# smartmeter.net
KiCad netlist of a schematic drawn in EAGLE
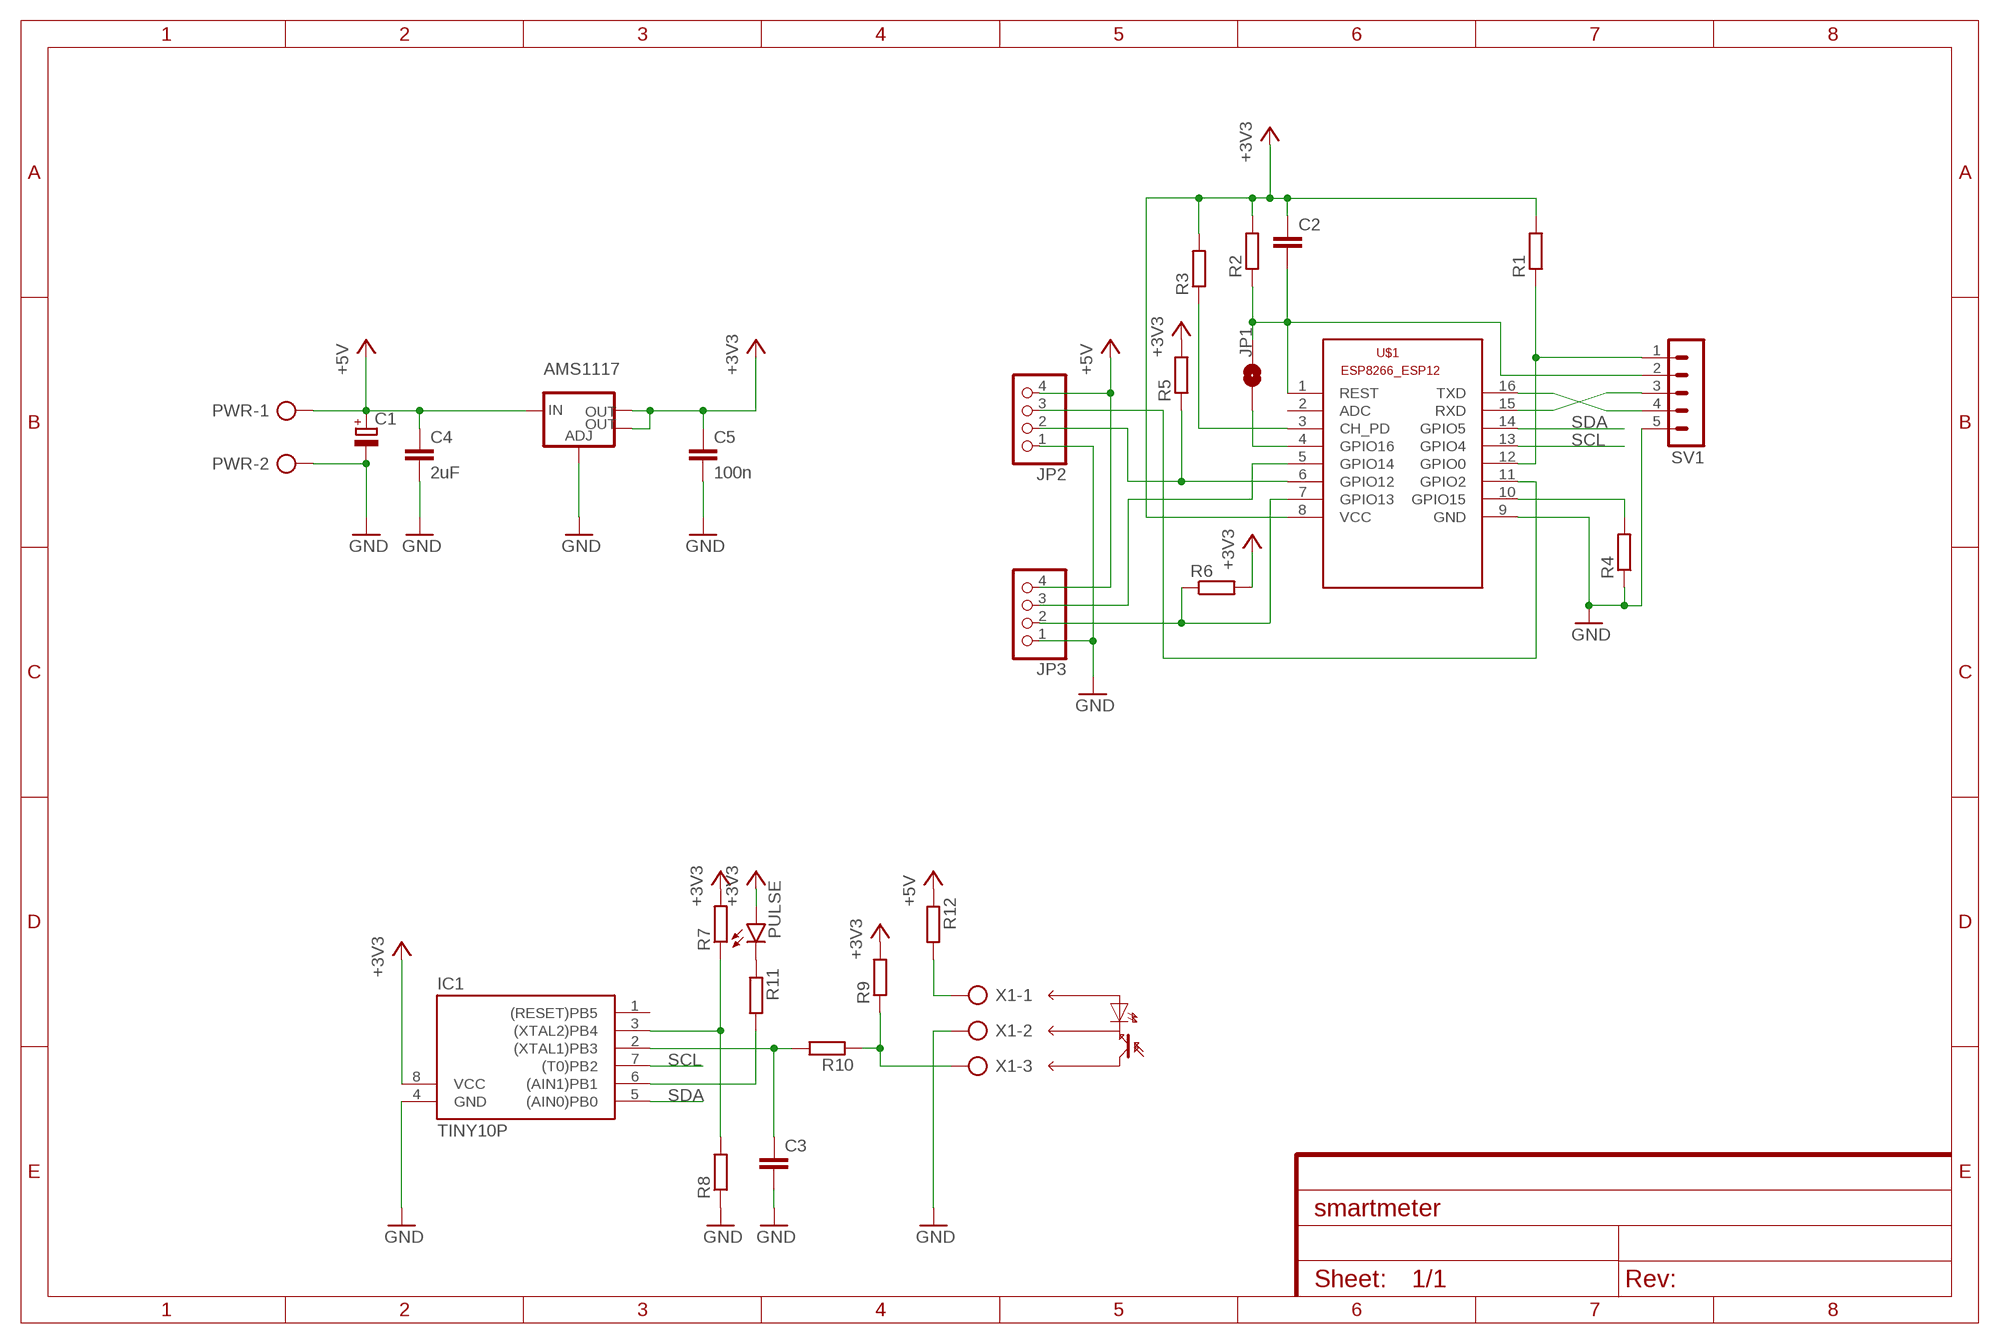
[diagram p0: schematic, sheet 1]

(export (version "E")
  (design (tool "Eeschema 10.0.6"))
  (components
    (comp (ref "AMS1117")
      (value "V_REG_LM1117SOT223")
      (footprint "eagle-import:SOT223")
      (libsource (lib "eagle-import") (part "V_REG_LM1117SOT223"))
    )
    (comp (ref "C1")
      (value "CPOL-EUE3.5-10")
      (footprint "eagle-import:E3,5-10")
      (libsource (lib "eagle-import") (part "CPOL-EUE3.5-10"))
    )
    (comp (ref "C2")
      (value "C-EU050-025X075")
      (footprint "eagle-import:C050-025X075")
      (libsource (lib "eagle-import") (part "C-EU050-025X075"))
    )
    (comp (ref "C3")
      (value "C-EU050-025X075")
      (footprint "eagle-import:C050-025X075")
      (libsource (lib "eagle-import") (part "C-EU050-025X075"))
    )
    (comp (ref "C4")
      (value "2uF")
      (footprint "eagle-import:C025-025X050")
      (libsource (lib "eagle-import") (part "C-EU025-025X050"))
    )
    (comp (ref "C5")
      (value "100n")
      (footprint "eagle-import:C025-025X050")
      (libsource (lib "eagle-import") (part "C-EU025-025X050"))
    )
    (comp (ref "IC1")
      (value "TINY10P")
      (footprint "eagle-import:DIL08")
      (libsource (lib "eagle-import") (part "TINY10P"))
    )
    (comp (ref "JP1")
      (value "JUMPER-SMT_2_NO_SILK")
      (footprint "eagle-import:SMT-JUMPER_2_NO_SILK")
      (libsource (lib "eagle-import") (part "JUMPER-SMT_2_NO_SILK"))
    )
    (comp (ref "JP2")
      (value "PINHD-1X4/90")
      (footprint "eagle-import:1X04_90")
      (libsource (lib "eagle-import") (part "PINHD-1X4/90"))
    )
    (comp (ref "JP3")
      (value "PINHD-1X4/90")
      (footprint "eagle-import:1X04_90")
      (libsource (lib "eagle-import") (part "PINHD-1X4/90"))
    )
    (comp (ref "PULSE")
      (value "LED5MM")
      (footprint "eagle-import:LED5MM")
      (libsource (lib "eagle-import") (part "LED5MM"))
    )
    (comp (ref "PWR")
      (value "AK500/2")
      (footprint "eagle-import:AK500_2")
      (libsource (lib "eagle-import") (part "AK500/2"))
    )
    (comp (ref "R1")
      (value "R-EU_0207/10")
      (footprint "eagle-import:0207_10")
      (libsource (lib "eagle-import") (part "R-EU_0207/10"))
    )
    (comp (ref "R2")
      (value "R-EU_0207/10")
      (footprint "eagle-import:0207_10")
      (libsource (lib "eagle-import") (part "R-EU_0207/10"))
    )
    (comp (ref "R3")
      (value "R-EU_0207/10")
      (footprint "eagle-import:0207_10")
      (libsource (lib "eagle-import") (part "R-EU_0207/10"))
    )
    (comp (ref "R4")
      (value "R-EU_0207/10")
      (footprint "eagle-import:0207_10")
      (libsource (lib "eagle-import") (part "R-EU_0207/10"))
    )
    (comp (ref "R5")
      (value "R-EU_0207/10")
      (footprint "eagle-import:0207_10")
      (libsource (lib "eagle-import") (part "R-EU_0207/10"))
    )
    (comp (ref "R6")
      (value "R-EU_0207/10")
      (footprint "eagle-import:0207_10")
      (libsource (lib "eagle-import") (part "R-EU_0207/10"))
    )
    (comp (ref "R7")
      (value "R-EU_0207/10")
      (footprint "eagle-import:0207_10")
      (libsource (lib "eagle-import") (part "R-EU_0207/10"))
    )
    (comp (ref "R8")
      (value "R-EU_0207/10")
      (footprint "eagle-import:0207_10")
      (libsource (lib "eagle-import") (part "R-EU_0207/10"))
    )
    (comp (ref "R9")
      (value "R-EU_0207/10")
      (footprint "eagle-import:0207_10")
      (libsource (lib "eagle-import") (part "R-EU_0207/10"))
    )
    (comp (ref "R10")
      (value "R-EU_0207/10")
      (footprint "eagle-import:0207_10")
      (libsource (lib "eagle-import") (part "R-EU_0207/10"))
    )
    (comp (ref "R11")
      (value "R-EU_0207/10")
      (footprint "eagle-import:0207_10")
      (libsource (lib "eagle-import") (part "R-EU_0207/10"))
    )
    (comp (ref "R12")
      (value "R-EU_0207/10")
      (footprint "eagle-import:0207_10")
      (libsource (lib "eagle-import") (part "R-EU_0207/10"))
    )
    (comp (ref "SV1")
      (value "MA05-1")
      (footprint "eagle-import:MA05-1")
      (libsource (lib "eagle-import") (part "MA05-1"))
    )
    (comp (ref "U$1")
      (value "ESP8266-12")
      (footprint "eagle-import:ESP8266-ESP12")
      (libsource (lib "eagle-import") (part "ESP8266-12"))
    )
    (comp (ref "X1")
      (value "AK500/3")
      (footprint "eagle-import:AK500_3")
      (libsource (lib "eagle-import") (part "AK500/3"))
    )
  )
  (nets
    (net (code "1") (name "+3V3") (class "Default")
      (node (ref "AMS1117") (pin "2") (pinfunction "OUT_2") (pintype "output"))
      (node (ref "AMS1117") (pin "4") (pinfunction "OUT_4") (pintype "output"))
      (node (ref "C2") (pin "1") (pinfunction "1_1") (pintype "passive"))
      (node (ref "C5") (pin "1") (pinfunction "1_1") (pintype "passive"))
      (node (ref "IC1") (pin "8") (pinfunction "VCC_8") (pintype "power_in"))
      (node (ref "PULSE") (pin "A") (pinfunction "A_A") (pintype "passive"))
      (node (ref "R1") (pin "2") (pinfunction "2_2") (pintype "passive"))
      (node (ref "R2") (pin "2") (pinfunction "2_2") (pintype "passive"))
      (node (ref "R3") (pin "2") (pinfunction "2_2") (pintype "passive"))
      (node (ref "R5") (pin "2") (pinfunction "2_2") (pintype "passive"))
      (node (ref "R6") (pin "2") (pinfunction "2_2") (pintype "passive"))
      (node (ref "R7") (pin "2") (pinfunction "2_2") (pintype "passive"))
      (node (ref "R9") (pin "2") (pinfunction "2_2") (pintype "passive"))
      (node (ref "U$1") (pin "8") (pinfunction "VCC_8") (pintype "bidirectional"))
    )
    (net (code "2") (name "+5V") (class "Default")
      (node (ref "AMS1117") (pin "3") (pinfunction "IN_3") (pintype "input"))
      (node (ref "C1") (pin "+") (pinfunction "+_+") (pintype "passive"))
      (node (ref "C4") (pin "1") (pinfunction "1_1") (pintype "passive"))
      (node (ref "JP2") (pin "4") (pinfunction "4_4") (pintype "passive"))
      (node (ref "JP3") (pin "4") (pinfunction "4_4") (pintype "passive"))
      (node (ref "PWR") (pin "1") (pinfunction "KL_1") (pintype "passive"))
      (node (ref "R12") (pin "1") (pinfunction "1_1") (pintype "passive"))
    )
    (net (code "3") (name "/SCL") (class "Default")
      (node (ref "IC1") (pin "7") (pinfunction "(T0)PB2_7") (pintype "bidirectional"))
      (node (ref "U$1") (pin "13") (pinfunction "GPIO4_13") (pintype "bidirectional"))
    )
    (net (code "4") (name "/SDA") (class "Default")
      (node (ref "IC1") (pin "5") (pinfunction "(AIN0)PB0_5") (pintype "bidirectional"))
      (node (ref "U$1") (pin "14") (pinfunction "GPIO5_14") (pintype "bidirectional"))
    )
    (net (code "5") (name "GND") (class "Default")
      (node (ref "AMS1117") (pin "1") (pinfunction "ADJ_1") (pintype "input"))
      (node (ref "C1") (pin "-") (pinfunction "-_-") (pintype "passive"))
      (node (ref "C3") (pin "2") (pinfunction "2_2") (pintype "passive"))
      (node (ref "C4") (pin "2") (pinfunction "2_2") (pintype "passive"))
      (node (ref "C5") (pin "2") (pinfunction "2_2") (pintype "passive"))
      (node (ref "IC1") (pin "4") (pinfunction "GND_4") (pintype "power_in"))
      (node (ref "JP2") (pin "1") (pinfunction "1_1") (pintype "passive"))
      (node (ref "JP3") (pin "1") (pinfunction "1_1") (pintype "passive"))
      (node (ref "PWR") (pin "2") (pinfunction "KL_2") (pintype "passive"))
      (node (ref "R4") (pin "1") (pinfunction "1_1") (pintype "passive"))
      (node (ref "R8") (pin "1") (pinfunction "1_1") (pintype "passive"))
      (node (ref "SV1") (pin "5") (pinfunction "5_5") (pintype "passive"))
      (node (ref "U$1") (pin "9") (pinfunction "GND_9") (pintype "bidirectional"))
      (node (ref "X1") (pin "2") (pinfunction "KL_2") (pintype "passive"))
    )
    (net (code "6") (name "Net-(IC1-(AIN1)PB1)") (class "Default")
      (node (ref "IC1") (pin "6") (pinfunction "(AIN1)PB1_6") (pintype "bidirectional"))
      (node (ref "R11") (pin "2") (pinfunction "2_2") (pintype "passive"))
    )
    (net (code "7") (name "Net-(IC1-(XTAL1)PB3)") (class "Default")
      (node (ref "C3") (pin "1") (pinfunction "1_1") (pintype "passive"))
      (node (ref "IC1") (pin "2") (pinfunction "(XTAL1)PB3_2") (pintype "bidirectional"))
      (node (ref "R10") (pin "2") (pinfunction "2_2") (pintype "passive"))
    )
    (net (code "8") (name "Net-(IC1-(XTAL2)PB4)") (class "Default")
      (node (ref "IC1") (pin "3") (pinfunction "(XTAL2)PB4_3") (pintype "bidirectional"))
      (node (ref "R7") (pin "1") (pinfunction "1_1") (pintype "passive"))
      (node (ref "R8") (pin "2") (pinfunction "2_2") (pintype "passive"))
    )
    (net (code "9") (name "Net-(PULSE-C)") (class "Default")
      (node (ref "PULSE") (pin "K") (pinfunction "C_K") (pintype "passive"))
      (node (ref "R11") (pin "1") (pinfunction "1_1") (pintype "passive"))
    )
    (net (code "10") (name "Net-(U$1-CH_PD)") (class "Default")
      (node (ref "R3") (pin "1") (pinfunction "1_1") (pintype "passive"))
      (node (ref "U$1") (pin "3") (pinfunction "CH_PD_3") (pintype "bidirectional"))
    )
    (net (code "11") (name "Net-(U$1-GPIO0)") (class "Default")
      (node (ref "R1") (pin "1") (pinfunction "1_1") (pintype "passive"))
      (node (ref "SV1") (pin "1") (pinfunction "1_1") (pintype "passive"))
      (node (ref "U$1") (pin "12") (pinfunction "GPIO0_12") (pintype "bidirectional"))
    )
    (net (code "12") (name "Net-(U$1-GPIO2)") (class "Default")
      (node (ref "JP2") (pin "3") (pinfunction "3_3") (pintype "passive"))
      (node (ref "U$1") (pin "11") (pinfunction "GPIO2_11") (pintype "bidirectional"))
    )
    (net (code "13") (name "Net-(U$1-GPIO12)") (class "Default")
      (node (ref "JP2") (pin "2") (pinfunction "2_2") (pintype "passive"))
      (node (ref "R5") (pin "1") (pinfunction "1_1") (pintype "passive"))
      (node (ref "U$1") (pin "6") (pinfunction "GPIO12_6") (pintype "bidirectional"))
    )
    (net (code "14") (name "Net-(U$1-GPIO13)") (class "Default")
      (node (ref "JP3") (pin "2") (pinfunction "2_2") (pintype "passive"))
      (node (ref "R6") (pin "1") (pinfunction "1_1") (pintype "passive"))
      (node (ref "U$1") (pin "7") (pinfunction "GPIO13_7") (pintype "bidirectional"))
    )
    (net (code "15") (name "Net-(U$1-GPIO14)") (class "Default")
      (node (ref "JP3") (pin "3") (pinfunction "3_3") (pintype "passive"))
      (node (ref "U$1") (pin "5") (pinfunction "GPIO14_5") (pintype "bidirectional"))
    )
    (net (code "16") (name "Net-(U$1-GPIO15)") (class "Default")
      (node (ref "R4") (pin "2") (pinfunction "2_2") (pintype "passive"))
      (node (ref "U$1") (pin "10") (pinfunction "GPIO15_10") (pintype "bidirectional"))
    )
    (net (code "17") (name "Net-(U$1-GPIO16)") (class "Default")
      (node (ref "JP1") (pin "1") (pinfunction "1_1") (pintype "passive"))
      (node (ref "U$1") (pin "4") (pinfunction "GPIO16_4") (pintype "bidirectional"))
    )
    (net (code "18") (name "Net-(U$1-REST)") (class "Default")
      (node (ref "C2") (pin "2") (pinfunction "2_2") (pintype "passive"))
      (node (ref "JP1") (pin "2") (pinfunction "2_2") (pintype "passive"))
      (node (ref "R2") (pin "1") (pinfunction "1_1") (pintype "passive"))
      (node (ref "SV1") (pin "2") (pinfunction "2_2") (pintype "passive"))
      (node (ref "U$1") (pin "1") (pinfunction "REST_1") (pintype "bidirectional"))
    )
    (net (code "19") (name "Net-(U$1-RXD)") (class "Default")
      (node (ref "SV1") (pin "3") (pinfunction "3_3") (pintype "passive"))
      (node (ref "U$1") (pin "15") (pinfunction "RXD_15") (pintype "bidirectional"))
    )
    (net (code "20") (name "Net-(U$1-TXD)") (class "Default")
      (node (ref "SV1") (pin "4") (pinfunction "4_4") (pintype "passive"))
      (node (ref "U$1") (pin "16") (pinfunction "TXD_16") (pintype "bidirectional"))
    )
    (net (code "21") (name "Net-(X1A-KL)") (class "Default")
      (node (ref "R12") (pin "2") (pinfunction "2_2") (pintype "passive"))
      (node (ref "X1") (pin "1") (pinfunction "KL_1") (pintype "passive"))
    )
    (net (code "22") (name "Net-(X1C-KL)") (class "Default")
      (node (ref "R10") (pin "1") (pinfunction "1_1") (pintype "passive"))
      (node (ref "R9") (pin "1") (pinfunction "1_1") (pintype "passive"))
      (node (ref "X1") (pin "3") (pinfunction "KL_3") (pintype "passive"))
    )
    (net (code "23") (name "unconnected-(IC1-(RESET)PB5-Pad1)") (class "Default")
      (node (ref "IC1") (pin "1") (pinfunction "(RESET)PB5_1") (pintype "bidirectional"))
    )
    (net (code "24") (name "unconnected-(U$1-ADC-Pad2)") (class "Default")
      (node (ref "U$1") (pin "2") (pinfunction "ADC_2") (pintype "bidirectional"))
    )
  )
)
